# EE579_Skittles_sch.net
KiCad netlist of a schematic drawn in Altium Designer
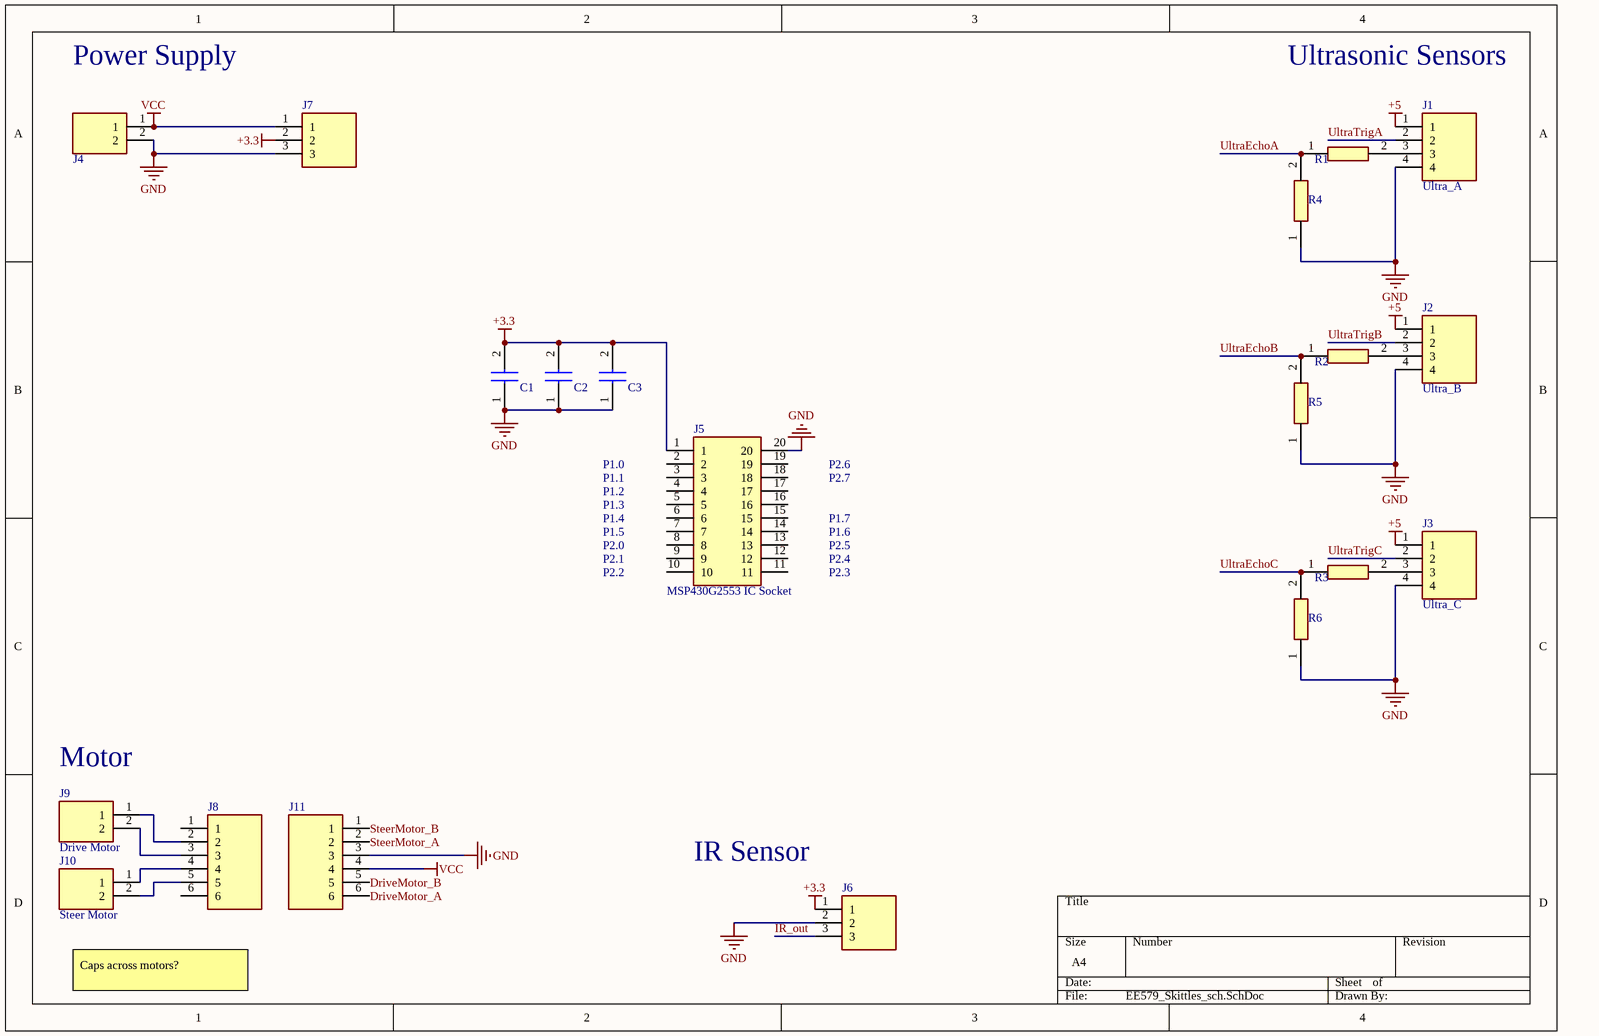
[diagram p0: EE579_Skittles_sch.SchDoc]

(export (version "E")
  (design (tool "Eeschema 10.0.6"))
  (components
    (comp (ref "C1")
      (value "21A106KQFNNNG")
      (footprint "PCB_lib:CAPC2012X135N")
      (description "Capacitor")
      (fields
        (field (name "MANUFACTURER_PART_NUMBER") "CL21A106KQFNNNG")
        (field (name "MOUSER PART NUMBER") "187-CL21A106KQFNNNG")
      )
      (libsource (lib "*") (part "CL21A106KQFNNNG"))
    )
    (comp (ref "C2")
      (value "CL21B105KPFNNNE")
      (footprint "PCB_lib:CAPC2012X135N")
      (description "Capacitor")
      (fields (field (name "MOUSER PART NUMBER") "187-CL21B105KPFNNNE"))
      (libsource (lib "*") (part "CL21B105KPFNNNE"))
    )
    (comp (ref "C3")
      (value "CC0805KPX7R9BB104")
      (footprint "PCB_lib:CAPC2012X95N")
      (description "Capacitor")
      (fields (field (name "MOUSER PART NUMBER") "603-CC805KPX7R9BB104"))
      (libsource (lib "*") (part "CC0805KPX7R9BB104"))
    )
    (comp (ref "J1")
      (value "Ultra_A")
      (footprint "PCB_lib:SHDR4W64P0X250_1X4_1240X575X700P")
      (description "Connector")
      (fields (field (name "MANUFACTURER_PART_NUMBER") "B4B-XH-A (LF)(SN)"))
      (libsource (lib "*") (part "B4B-XH-A__LF__SN_"))
    )
    (comp (ref "J2")
      (value "Ultra_B")
      (footprint "PCB_lib:SHDR4W64P0X250_1X4_1240X575X700P")
      (description "Connector")
      (fields (field (name "MANUFACTURER_PART_NUMBER") "B4B-XH-A (LF)(SN)"))
      (libsource (lib "*") (part "B4B-XH-A__LF__SN_"))
    )
    (comp (ref "J3")
      (value "Ultra_C")
      (footprint "PCB_lib:SHDR4W64P0X250_1X4_1240X575X700P")
      (description "Connector")
      (fields (field (name "MANUFACTURER_PART_NUMBER") "B4B-XH-A (LF)(SN)"))
      (libsource (lib "*") (part "B4B-XH-A__LF__SN_"))
    )
    (comp (ref "J4")
      (value "B2B-PH-K-S_LF__SN_")
      (footprint "PCB_lib:SHDR2W50P0X200_1X2_590X450X600P")
      (description "Connector")
      (fields (field (name "MANUFACTURER_PART_NUMBER") "B2B-PH-K-S(LF)(SN)"))
      (libsource (lib "*") (part "B2B-PH-K-S_LF__SN_"))
    )
    (comp (ref "J5")
      (value "MSP430G2553 IC Socket")
      (footprint "PCB_lib:DIPS762W70P254L2540H510Q20N")
      (description "Connector")
      (fields
        (field (name "MANUFACTURER_PART_NUMBER") "1-2199298-6")
        (field (name "MOUSER PART NUMBER") "571-1-2199298-6")
      )
      (libsource (lib "*") (part "1-2199298-6"))
    )
    (comp (ref "J6")
      (value "B3B-XH-A__LF__SN_")
      (footprint "PCB_lib:SHDR3W64P0X250_1X3_990X575X700P")
      (description "Connector")
      (fields (field (name "MANUFACTURER_PART_NUMBER") "B3B-XH-A (LF)(SN)"))
      (libsource (lib "*") (part "B3B-XH-A__LF__SN_"))
    )
    (comp (ref "J7")
      (value "801-87-003-10-001101")
      (footprint "PCB_lib:RHDR3W60P0X254_1X3_762X254X700P")
      (description "Connector")
      (fields (field (name "MOUSER PART NUMBER") "437-8018700310001101"))
      (libsource (lib "*") (part "801-87-003-10-001101"))
    )
    (comp (ref "J8")
      (value "61300611821")
      (footprint "RHDR6W97P0X254_1X6_1574X250X865P")
      (description "WURTH ELEKTRONIK - 61300611821 - PCB Receptacle")
      (fields (field (name "MOUSER PART NUMBER") "710-61300611821"))
      (libsource (lib "") (part "61300611821_1"))
    )
    (comp (ref "J9")
      (value "Drive Motor")
      (footprint "PCB_lib:SHDR2W50P0X200_1X2_590X450X600P")
      (description "Connector")
      (fields (field (name "MANUFACTURER_PART_NUMBER") "B2B-PH-K-S(LF)(SN)"))
      (libsource (lib "*") (part "B2B-PH-K-S_LF__SN_"))
    )
    (comp (ref "J10")
      (value "Steer Motor")
      (footprint "PCB_lib:SHDR2W50P0X200_1X2_590X450X600P")
      (description "Connector")
      (fields (field (name "MANUFACTURER_PART_NUMBER") "B2B-PH-K-S(LF)(SN)"))
      (libsource (lib "*") (part "B2B-PH-K-S_LF__SN_"))
    )
    (comp (ref "J11")
      (value "61300611821")
      (footprint "RHDR6W97P0X254_1X6_1574X250X865P")
      (description "WURTH ELEKTRONIK - 61300611821 - PCB Receptacle")
      (fields (field (name "MOUSER PART NUMBER") "710-61300611821"))
      (libsource (lib "SCH_lib") (part "61300611821"))
    )
    (comp (ref "R1")
      (value "ERJ-PB6B3002V")
      (footprint "PCB_lib:RESC2012X70N")
      (description "Resistor")
      (fields (field (name "MOUSER PART NUMBER") "667-ERJ-PB6B3002V"))
      (libsource (lib "") (part "ERJ-PB6B3002V_1"))
    )
    (comp (ref "R2")
      (value "ERJ-PB6B3002V")
      (footprint "PCB_lib:RESC2012X70N")
      (description "Resistor")
      (fields (field (name "MOUSER PART NUMBER") "667-ERJ-PB6B3002V"))
      (libsource (lib "") (part "ERJ-PB6B3002V_1"))
    )
    (comp (ref "R3")
      (value "ERJ-PB6B3002V")
      (footprint "PCB_lib:RESC2012X70N")
      (description "Resistor")
      (fields (field (name "MOUSER PART NUMBER") "667-ERJ-PB6B3002V"))
      (libsource (lib "") (part "ERJ-PB6B3002V_1"))
    )
    (comp (ref "R4")
      (value "ERJ-PB6B3002V")
      (footprint "PCB_lib:RESC2012X70N")
      (description "Resistor")
      (fields (field (name "MOUSER PART NUMBER") "667-ERJ-PB6B3002V"))
      (libsource (lib "*") (part "ERJ-PB6B3002V"))
    )
    (comp (ref "R5")
      (value "ERJ-PB6B3002V")
      (footprint "PCB_lib:RESC2012X70N")
      (description "Resistor")
      (fields (field (name "MOUSER PART NUMBER") "667-ERJ-PB6B3002V"))
      (libsource (lib "*") (part "ERJ-PB6B3002V"))
    )
    (comp (ref "R6")
      (value "ERJ-PB6B3002V")
      (footprint "PCB_lib:RESC2012X70N")
      (description "Resistor")
      (fields (field (name "MOUSER PART NUMBER") "667-ERJ-PB6B3002V"))
      (libsource (lib "*") (part "ERJ-PB6B3002V"))
    )
  )
  (nets
    (net (code "1") (name "+3.3") (class "Default")
      (node (ref "C1") (pin "2") (pinfunction "2_2") (pintype "passive"))
      (node (ref "C2") (pin "2") (pinfunction "2_2") (pintype "passive"))
      (node (ref "C3") (pin "2") (pinfunction "2_2") (pintype "passive"))
      (node (ref "J5") (pin "1") (pinfunction "1_1") (pintype "passive"))
      (node (ref "J6") (pin "1") (pinfunction "1_1") (pintype "passive"))
      (node (ref "J7") (pin "2") (pinfunction "2_2") (pintype "passive"))
    )
    (net (code "2") (name "+5") (class "Default")
      (node (ref "J1") (pin "1") (pinfunction "1_1") (pintype "passive"))
      (node (ref "J2") (pin "1") (pinfunction "1_1") (pintype "passive"))
      (node (ref "J3") (pin "1") (pinfunction "1_1") (pintype "passive"))
    )
    (net (code "3") (name "/DriveMotor_A") (class "Default")
      (node (ref "J11") (pin "6") (pinfunction "6_6") (pintype "passive"))
    )
    (net (code "4") (name "/DriveMotor_B") (class "Default")
      (node (ref "J11") (pin "5") (pinfunction "5_5") (pintype "passive"))
    )
    (net (code "5") (name "/IR_out") (class "Default")
      (node (ref "J6") (pin "3") (pinfunction "3_3") (pintype "passive"))
    )
    (net (code "6") (name "/SteerMotor_A") (class "Default")
      (node (ref "J11") (pin "2") (pinfunction "2_2") (pintype "passive"))
    )
    (net (code "7") (name "/SteerMotor_B") (class "Default")
      (node (ref "J11") (pin "1") (pinfunction "1_1") (pintype "passive"))
    )
    (net (code "8") (name "/UltraEchoA") (class "Default")
      (node (ref "R1") (pin "1") (pinfunction "1_1") (pintype "passive"))
      (node (ref "R4") (pin "2") (pinfunction "2_2") (pintype "passive"))
    )
    (net (code "9") (name "/UltraEchoB") (class "Default")
      (node (ref "R2") (pin "1") (pinfunction "1_1") (pintype "passive"))
      (node (ref "R5") (pin "2") (pinfunction "2_2") (pintype "passive"))
    )
    (net (code "10") (name "/UltraEchoC") (class "Default")
      (node (ref "R3") (pin "1") (pinfunction "1_1") (pintype "passive"))
      (node (ref "R6") (pin "2") (pinfunction "2_2") (pintype "passive"))
    )
    (net (code "11") (name "/UltraTrigA") (class "Default")
      (node (ref "J1") (pin "2") (pinfunction "2_2") (pintype "passive"))
    )
    (net (code "12") (name "/UltraTrigB") (class "Default")
      (node (ref "J2") (pin "2") (pinfunction "2_2") (pintype "passive"))
    )
    (net (code "13") (name "/UltraTrigC") (class "Default")
      (node (ref "J3") (pin "2") (pinfunction "2_2") (pintype "passive"))
    )
    (net (code "14") (name "GND") (class "Default")
      (node (ref "C1") (pin "1") (pinfunction "1_1") (pintype "passive"))
      (node (ref "C2") (pin "1") (pinfunction "1_1") (pintype "passive"))
      (node (ref "C3") (pin "1") (pinfunction "1_1") (pintype "passive"))
      (node (ref "J1") (pin "4") (pinfunction "4_4") (pintype "passive"))
      (node (ref "J11") (pin "3") (pinfunction "3_3") (pintype "passive"))
      (node (ref "J2") (pin "4") (pinfunction "4_4") (pintype "passive"))
      (node (ref "J3") (pin "4") (pinfunction "4_4") (pintype "passive"))
      (node (ref "J4") (pin "2") (pinfunction "2_2") (pintype "passive"))
      (node (ref "J5") (pin "20") (pinfunction "20_20") (pintype "passive"))
      (node (ref "J6") (pin "2") (pinfunction "2_2") (pintype "passive"))
      (node (ref "J7") (pin "3") (pinfunction "3_3") (pintype "passive"))
      (node (ref "R4") (pin "1") (pinfunction "1_1") (pintype "passive"))
      (node (ref "R5") (pin "1") (pinfunction "1_1") (pintype "passive"))
      (node (ref "R6") (pin "1") (pinfunction "1_1") (pintype "passive"))
    )
    (net (code "15") (name "Net-(J1-Pad3)") (class "Default")
      (node (ref "J1") (pin "3") (pinfunction "3_3") (pintype "passive"))
      (node (ref "R1") (pin "2") (pinfunction "2_2") (pintype "passive"))
    )
    (net (code "16") (name "Net-(J2-Pad3)") (class "Default")
      (node (ref "J2") (pin "3") (pinfunction "3_3") (pintype "passive"))
      (node (ref "R2") (pin "2") (pinfunction "2_2") (pintype "passive"))
    )
    (net (code "17") (name "Net-(J3-Pad3)") (class "Default")
      (node (ref "J3") (pin "3") (pinfunction "3_3") (pintype "passive"))
      (node (ref "R3") (pin "2") (pinfunction "2_2") (pintype "passive"))
    )
    (net (code "18") (name "Net-(J8-Pad2)") (class "Default")
      (node (ref "J8") (pin "2") (pinfunction "2_2") (pintype "passive"))
      (node (ref "J9") (pin "1") (pinfunction "1_1") (pintype "passive"))
    )
    (net (code "19") (name "Net-(J8-Pad3)") (class "Default")
      (node (ref "J8") (pin "3") (pinfunction "3_3") (pintype "passive"))
      (node (ref "J9") (pin "2") (pinfunction "2_2") (pintype "passive"))
    )
    (net (code "20") (name "Net-(J10-Pad1)") (class "Default")
      (node (ref "J10") (pin "1") (pinfunction "1_1") (pintype "passive"))
      (node (ref "J8") (pin "4") (pinfunction "4_4") (pintype "passive"))
    )
    (net (code "21") (name "Net-(J10-Pad2)") (class "Default")
      (node (ref "J10") (pin "2") (pinfunction "2_2") (pintype "passive"))
      (node (ref "J8") (pin "5") (pinfunction "5_5") (pintype "passive"))
    )
    (net (code "22") (name "VCC") (class "Default")
      (node (ref "J11") (pin "4") (pinfunction "4_4") (pintype "passive"))
      (node (ref "J4") (pin "1") (pinfunction "1_1") (pintype "passive"))
      (node (ref "J7") (pin "1") (pinfunction "1_1") (pintype "passive"))
    )
    (net (code "23") (name "unconnected-(J5-Pad2)") (class "Default")
      (node (ref "J5") (pin "2") (pinfunction "2_2") (pintype "passive"))
    )
    (net (code "24") (name "unconnected-(J5-Pad3)") (class "Default")
      (node (ref "J5") (pin "3") (pinfunction "3_3") (pintype "passive"))
    )
    (net (code "25") (name "unconnected-(J5-Pad4)") (class "Default")
      (node (ref "J5") (pin "4") (pinfunction "4_4") (pintype "passive"))
    )
    (net (code "26") (name "unconnected-(J5-Pad5)") (class "Default")
      (node (ref "J5") (pin "5") (pinfunction "5_5") (pintype "passive"))
    )
    (net (code "27") (name "unconnected-(J5-Pad6)") (class "Default")
      (node (ref "J5") (pin "6") (pinfunction "6_6") (pintype "passive"))
    )
    (net (code "28") (name "unconnected-(J5-Pad7)") (class "Default")
      (node (ref "J5") (pin "7") (pinfunction "7_7") (pintype "passive"))
    )
    (net (code "29") (name "unconnected-(J5-Pad8)") (class "Default")
      (node (ref "J5") (pin "8") (pinfunction "8_8") (pintype "passive"))
    )
    (net (code "30") (name "unconnected-(J5-Pad9)") (class "Default")
      (node (ref "J5") (pin "9") (pinfunction "9_9") (pintype "passive"))
    )
    (net (code "31") (name "unconnected-(J5-Pad10)") (class "Default")
      (node (ref "J5") (pin "10") (pinfunction "10_10") (pintype "passive"))
    )
    (net (code "32") (name "unconnected-(J5-Pad11)") (class "Default")
      (node (ref "J5") (pin "11") (pinfunction "11_11") (pintype "passive"))
    )
    (net (code "33") (name "unconnected-(J5-Pad12)") (class "Default")
      (node (ref "J5") (pin "12") (pinfunction "12_12") (pintype "passive"))
    )
    (net (code "34") (name "unconnected-(J5-Pad13)") (class "Default")
      (node (ref "J5") (pin "13") (pinfunction "13_13") (pintype "passive"))
    )
    (net (code "35") (name "unconnected-(J5-Pad14)") (class "Default")
      (node (ref "J5") (pin "14") (pinfunction "14_14") (pintype "passive"))
    )
    (net (code "36") (name "unconnected-(J5-Pad15)") (class "Default")
      (node (ref "J5") (pin "15") (pinfunction "15_15") (pintype "passive"))
    )
    (net (code "37") (name "unconnected-(J5-Pad16)") (class "Default")
      (node (ref "J5") (pin "16") (pinfunction "16_16") (pintype "passive"))
    )
    (net (code "38") (name "unconnected-(J5-Pad17)") (class "Default")
      (node (ref "J5") (pin "17") (pinfunction "17_17") (pintype "passive"))
    )
    (net (code "39") (name "unconnected-(J5-Pad18)") (class "Default")
      (node (ref "J5") (pin "18") (pinfunction "18_18") (pintype "passive"))
    )
    (net (code "40") (name "unconnected-(J5-Pad19)") (class "Default")
      (node (ref "J5") (pin "19") (pinfunction "19_19") (pintype "passive"))
    )
    (net (code "41") (name "unconnected-(J8-Pad1)") (class "Default")
      (node (ref "J8") (pin "1") (pinfunction "1_1") (pintype "passive"))
    )
    (net (code "42") (name "unconnected-(J8-Pad6)") (class "Default")
      (node (ref "J8") (pin "6") (pinfunction "6_6") (pintype "passive"))
    )
  )
)
